# tm8_first.net
KiCad netlist of a schematic drawn in EAGLE
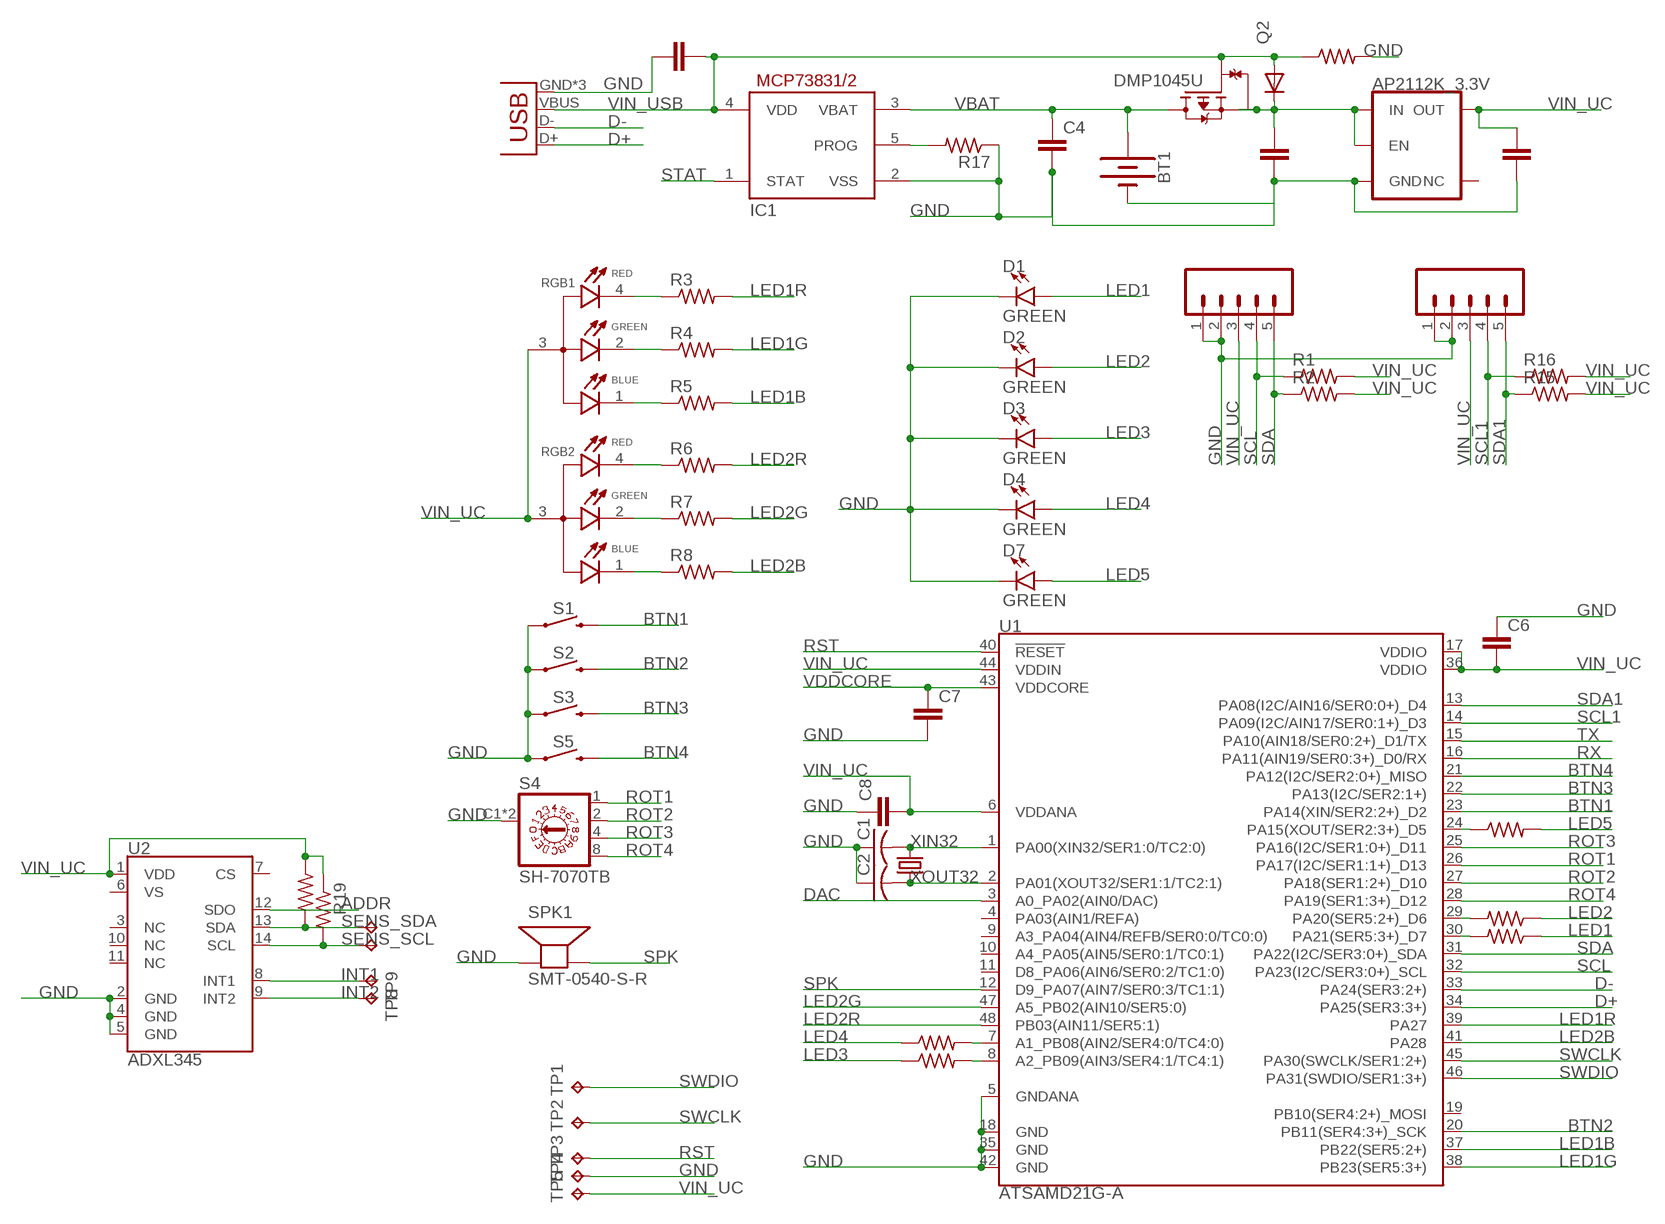
[diagram p0: schematic, sheet 1]

(export (version "E")
  (design (tool "Eeschema 10.0.6"))
  (components
    (comp (ref "AP2112K_3.3V")
      (value "3.3V")
      (footprint "eagle-import:SOT23-5")
      (libsource (lib "eagle-import") (part "V_REG_AP2112K-3.3V"))
    )
    (comp (ref "BT1")
      (value "BATTERY-20MM_SMD_4LEGS_OVERPASTE_INNER")
      (footprint "eagle-import:BATTCON_20MM_4LEGS_OVERPASTE_INNER")
      (libsource (lib "eagle-import") (part "BATTERY-20MM_SMD_4LEGS_OVERPASTE_INNER"))
    )
    (comp (ref "C1")
      (value "C-USC0603")
      (footprint "eagle-import:C0603")
      (libsource (lib "eagle-import") (part "C-USC0603"))
    )
    (comp (ref "C2")
      (value "C-USC0603")
      (footprint "eagle-import:C0603")
      (libsource (lib "eagle-import") (part "C-USC0603"))
    )
    (comp (ref "C3")
      (value "C-EUC0603")
      (footprint "eagle-import:C0603")
      (libsource (lib "eagle-import") (part "C-EUC0603"))
    )
    (comp (ref "C4")
      (value "C-EUC0603")
      (footprint "eagle-import:C0603")
      (libsource (lib "eagle-import") (part "C-EUC0603"))
    )
    (comp (ref "C5")
      (value "C-EUC0603")
      (footprint "eagle-import:C0603")
      (libsource (lib "eagle-import") (part "C-EUC0603"))
    )
    (comp (ref "C6")
      (value "C-EUC0603")
      (footprint "eagle-import:C0603")
      (libsource (lib "eagle-import") (part "C-EUC0603"))
    )
    (comp (ref "C7")
      (value "C-EUC0603")
      (footprint "eagle-import:C0603")
      (libsource (lib "eagle-import") (part "C-EUC0603"))
    )
    (comp (ref "C8")
      (value "C-EUC0603")
      (footprint "eagle-import:C0603")
      (libsource (lib "eagle-import") (part "C-EUC0603"))
    )
    (comp (ref "C9")
      (value "C-EUC0603")
      (footprint "eagle-import:C0603")
      (libsource (lib "eagle-import") (part "C-EUC0603"))
    )
    (comp (ref "D1")
      (value "GREEN")
      (footprint "eagle-import:LED-1206")
      (libsource (lib "eagle-import") (part "LED-GREEN1206"))
    )
    (comp (ref "D2")
      (value "GREEN")
      (footprint "eagle-import:LED-1206")
      (libsource (lib "eagle-import") (part "LED-GREEN1206"))
    )
    (comp (ref "D3")
      (value "GREEN")
      (footprint "eagle-import:LED-1206")
      (libsource (lib "eagle-import") (part "LED-GREEN1206"))
    )
    (comp (ref "D4")
      (value "GREEN")
      (footprint "eagle-import:LED-1206")
      (libsource (lib "eagle-import") (part "LED-GREEN1206"))
    )
    (comp (ref "D7")
      (value "GREEN")
      (footprint "eagle-import:LED-1206")
      (libsource (lib "eagle-import") (part "LED-GREEN1206"))
    )
    (comp (ref "D8")
      (value "DIODESOD-323F")
      (footprint "eagle-import:SOD-323F")
      (libsource (lib "eagle-import") (part "DIODESOD-323F"))
    )
    (comp (ref "IC1")
      (value "MCP73831/OT")
      (footprint "eagle-import:SOT23-5L")
      (libsource (lib "eagle-import") (part "MCP73831/OT"))
    )
    (comp (ref "JP2")
      (value "USB-MICROB")
      (footprint "eagle-import:USB-MICROB")
      (libsource (lib "eagle-import") (part "USB-MICROB"))
    )
    (comp (ref "LCD1")
      (value "CONN_05VERT_FEMALE_HEADER")
      (footprint "eagle-import:1X05_SMD_VERTICAL_COMBO")
      (libsource (lib "eagle-import") (part "CONN_05VERT_FEMALE_HEADER"))
    )
    (comp (ref "LCD2")
      (value "CONN_05VERT_FEMALE_HEADER")
      (footprint "eagle-import:1X05_SMD_VERTICAL_COMBO")
      (libsource (lib "eagle-import") (part "CONN_05VERT_FEMALE_HEADER"))
    )
    (comp (ref "Q2")
      (value "DMP1045U")
      (footprint "eagle-import:SOT91P240X110-3N")
      (fields (field (name "MF") "Diodes Inc."))
      (libsource (lib "eagle-import") (part "DMP1045U"))
    )
    (comp (ref "R1")
      (value "R-US_R0603")
      (footprint "eagle-import:R0603")
      (libsource (lib "eagle-import") (part "rcl_334_R-US_R0603"))
    )
    (comp (ref "R2")
      (value "R-US_R0603")
      (footprint "eagle-import:R0603")
      (libsource (lib "eagle-import") (part "rcl_334_R-US_R0603"))
    )
    (comp (ref "R3")
      (value "R-US_R0603")
      (footprint "eagle-import:R0603")
      (libsource (lib "eagle-import") (part "rcl_334_R-US_R0603"))
    )
    (comp (ref "R4")
      (value "R-US_R0603")
      (footprint "eagle-import:R0603")
      (libsource (lib "eagle-import") (part "rcl_334_R-US_R0603"))
    )
    (comp (ref "R5")
      (value "R-US_R0603")
      (footprint "eagle-import:R0603")
      (libsource (lib "eagle-import") (part "rcl_334_R-US_R0603"))
    )
    (comp (ref "R6")
      (value "R-US_R0603")
      (footprint "eagle-import:R0603")
      (libsource (lib "eagle-import") (part "rcl_334_R-US_R0603"))
    )
    (comp (ref "R7")
      (value "R-US_R0603")
      (footprint "eagle-import:R0603")
      (libsource (lib "eagle-import") (part "rcl_334_R-US_R0603"))
    )
    (comp (ref "R8")
      (value "R-US_R0603")
      (footprint "eagle-import:R0603")
      (libsource (lib "eagle-import") (part "rcl_334_R-US_R0603"))
    )
    (comp (ref "R9")
      (value "R-US_R0603")
      (footprint "eagle-import:R0603")
      (libsource (lib "eagle-import") (part "rcl_334_R-US_R0603"))
    )
    (comp (ref "R10")
      (value "R-US_R0603")
      (footprint "eagle-import:R0603")
      (libsource (lib "eagle-import") (part "rcl_334_R-US_R0603"))
    )
    (comp (ref "R11")
      (value "R-US_R0603")
      (footprint "eagle-import:R0603")
      (libsource (lib "eagle-import") (part "rcl_334_R-US_R0603"))
    )
    (comp (ref "R12")
      (value "R-US_R0603")
      (footprint "eagle-import:R0603")
      (libsource (lib "eagle-import") (part "rcl_334_R-US_R0603"))
    )
    (comp (ref "R13")
      (value "R-US_R0603")
      (footprint "eagle-import:R0603")
      (libsource (lib "eagle-import") (part "rcl_334_R-US_R0603"))
    )
    (comp (ref "R14")
      (value "R-US_R0603")
      (footprint "eagle-import:R0603")
      (libsource (lib "eagle-import") (part "R-US_R0603"))
    )
    (comp (ref "R15")
      (value "R-US_R0603")
      (footprint "eagle-import:R0603")
      (libsource (lib "eagle-import") (part "rcl_334_R-US_R0603"))
    )
    (comp (ref "R16")
      (value "R-US_R0603")
      (footprint "eagle-import:R0603")
      (libsource (lib "eagle-import") (part "rcl_334_R-US_R0603"))
    )
    (comp (ref "R17")
      (value "R-US_R0603")
      (footprint "eagle-import:R0603")
      (libsource (lib "eagle-import") (part "adafruit_25768682_R-US_R0603"))
    )
    (comp (ref "R18")
      (value "R-US_R0603")
      (footprint "eagle-import:R0603")
      (libsource (lib "eagle-import") (part "rcl_334_R-US_R0603"))
    )
    (comp (ref "R19")
      (value "R-US_R0603")
      (footprint "eagle-import:R0603")
      (libsource (lib "eagle-import") (part "rcl_334_R-US_R0603"))
    )
    (comp (ref "RGB1")
      (value "EAST1616RGBA3")
      (footprint "eagle-import:LED_EAST1616RGBA3")
      (fields (field (name "MF") "Everlight Electronics"))
      (libsource (lib "eagle-import") (part "EAST1616RGBA3"))
    )
    (comp (ref "RGB2")
      (value "EAST1616RGBA3")
      (footprint "eagle-import:LED_EAST1616RGBA3")
      (fields (field (name "MF") "Everlight Electronics"))
      (libsource (lib "eagle-import") (part "EAST1616RGBA3"))
    )
    (comp (ref "S1")
      (value "MOMENTARY-SWITCH-SPST-SMD-6.0X3.5MM")
      (footprint "eagle-import:TACTILE_SWITCH_SMD_6.0X3.5MM")
      (libsource (lib "eagle-import") (part "MOMENTARY-SWITCH-SPST-SMD-6.0X3.5MM"))
    )
    (comp (ref "S2")
      (value "MOMENTARY-SWITCH-SPST-SMD-6.0X3.5MM")
      (footprint "eagle-import:TACTILE_SWITCH_SMD_6.0X3.5MM")
      (libsource (lib "eagle-import") (part "MOMENTARY-SWITCH-SPST-SMD-6.0X3.5MM"))
    )
    (comp (ref "S3")
      (value "MOMENTARY-SWITCH-SPST-SMD-6.0X3.5MM")
      (footprint "eagle-import:TACTILE_SWITCH_SMD_6.0X3.5MM")
      (libsource (lib "eagle-import") (part "MOMENTARY-SWITCH-SPST-SMD-6.0X3.5MM"))
    )
    (comp (ref "S4")
      (value "SH-7070TB")
      (footprint "eagle-import:SH-7070B")
      (fields (field (name "MF") "Nidec Copal"))
      (libsource (lib "eagle-import") (part "SH-7070TB"))
    )
    (comp (ref "S5")
      (value "MOMENTARY-SWITCH-SPST-SMD-6.0X3.5MM")
      (footprint "eagle-import:TACTILE_SWITCH_SMD_6.0X3.5MM")
      (libsource (lib "eagle-import") (part "MOMENTARY-SWITCH-SPST-SMD-6.0X3.5MM"))
    )
    (comp (ref "SPK1")
      (value "SMT-0540-S-R")
      (footprint "eagle-import:SMT-0540-S-R")
      (fields (field (name "MF") "PUI"))
      (libsource (lib "eagle-import") (part "SMT-0540-S-R"))
    )
    (comp (ref "TP1")
      (value "TPTP10R")
      (footprint "eagle-import:TP10R")
      (libsource (lib "eagle-import") (part "TPTP10R"))
    )
    (comp (ref "TP2")
      (value "TPTP10R")
      (footprint "eagle-import:TP10R")
      (libsource (lib "eagle-import") (part "TPTP10R"))
    )
    (comp (ref "TP3")
      (value "TPTP10R")
      (footprint "eagle-import:TP10R")
      (libsource (lib "eagle-import") (part "TPTP10R"))
    )
    (comp (ref "TP4")
      (value "TPTP10R")
      (footprint "eagle-import:TP10R")
      (libsource (lib "eagle-import") (part "TPTP10R"))
    )
    (comp (ref "TP5")
      (value "TPTP10R")
      (footprint "eagle-import:TP10R")
      (libsource (lib "eagle-import") (part "TPTP10R"))
    )
    (comp (ref "TP6")
      (value "TPTP10R")
      (footprint "eagle-import:TP10R")
      (libsource (lib "eagle-import") (part "TPTP10R"))
    )
    (comp (ref "TP7")
      (value "TPTP10R")
      (footprint "eagle-import:TP10R")
      (libsource (lib "eagle-import") (part "TPTP10R"))
    )
    (comp (ref "TP8")
      (value "TPTP10R")
      (footprint "eagle-import:TP10R")
      (libsource (lib "eagle-import") (part "TPTP10R"))
    )
    (comp (ref "TP9")
      (value "TPTP10R")
      (footprint "eagle-import:TP10R")
      (libsource (lib "eagle-import") (part "TPTP10R"))
    )
    (comp (ref "U1")
      (value "ATSAMD21G-A")
      (footprint "eagle-import:TQFP-48")
      (libsource (lib "eagle-import") (part "ATSAMD21G-A"))
    )
    (comp (ref "U2")
      (value "ADXL345")
      (footprint "eagle-import:LGA-14")
      (libsource (lib "eagle-import") (part "ADXL345"))
    )
    (comp (ref "Y1")
      (value "32.768kHz")
      (footprint "eagle-import:CRYSTAL-SMD-3.2X1.5MM")
      (libsource (lib "eagle-import") (part "CRYSTAL-32.768KHZSMD-3.2X1.5"))
    )
  )
  (nets
    (net (code "1") (name "/ADDR") (class "Default")
      (node (ref "U2") (pin "12") (pinfunction "SDO_12") (pintype "bidirectional"))
    )
    (net (code "2") (name "/BTN1") (class "Default")
      (node (ref "S1") (pin "2") (pinfunction "2_2") (pintype "passive"))
      (node (ref "U1") (pin "23") (pinfunction "PA14(XIN/SER2:2+)_D2_23") (pintype "bidirectional"))
    )
    (net (code "3") (name "/BTN2") (class "Default")
      (node (ref "S2") (pin "2") (pinfunction "2_2") (pintype "passive"))
      (node (ref "U1") (pin "20") (pinfunction "PB11(SER4:3+)_SCK_20") (pintype "bidirectional"))
    )
    (net (code "4") (name "/BTN3") (class "Default")
      (node (ref "S3") (pin "2") (pinfunction "2_2") (pintype "passive"))
      (node (ref "U1") (pin "22") (pinfunction "PA13(I2C/SER2:1+)_22") (pintype "bidirectional"))
    )
    (net (code "5") (name "/BTN4") (class "Default")
      (node (ref "S5") (pin "2") (pinfunction "2_2") (pintype "passive"))
      (node (ref "U1") (pin "21") (pinfunction "PA12(I2C/SER2:0+)_MISO_21") (pintype "bidirectional"))
    )
    (net (code "6") (name "/D+") (class "Default")
      (node (ref "JP2") (pin "D+") (pinfunction "D+_D+") (pintype "bidirectional"))
      (node (ref "U1") (pin "34") (pinfunction "PA25(SER3:3+)_34") (pintype "bidirectional"))
    )
    (net (code "7") (name "/D-") (class "Default")
      (node (ref "JP2") (pin "D-") (pinfunction "D-_D-") (pintype "bidirectional"))
      (node (ref "U1") (pin "33") (pinfunction "PA24(SER3:2+)_33") (pintype "bidirectional"))
    )
    (net (code "8") (name "/DAC") (class "Default")
      (node (ref "U1") (pin "3") (pinfunction "A0_PA02(AIN0/DAC)_3") (pintype "bidirectional"))
    )
    (net (code "9") (name "/GND") (class "Default")
      (node (ref "AP2112K_3.3V") (pin "2") (pinfunction "GND_2") (pintype "input"))
      (node (ref "BT1") (pin "2") (pinfunction "-_2") (pintype "power_in"))
      (node (ref "C1") (pin "1") (pinfunction "1_1") (pintype "passive"))
      (node (ref "C2") (pin "1") (pinfunction "1_1") (pintype "passive"))
      (node (ref "C3") (pin "1") (pinfunction "1_1") (pintype "passive"))
      (node (ref "C4") (pin "2") (pinfunction "2_2") (pintype "passive"))
      (node (ref "C5") (pin "2") (pinfunction "2_2") (pintype "passive"))
      (node (ref "C6") (pin "1") (pinfunction "1_1") (pintype "passive"))
      (node (ref "C7") (pin "2") (pinfunction "2_2") (pintype "passive"))
      (node (ref "C8") (pin "1") (pinfunction "1_1") (pintype "passive"))
      (node (ref "C9") (pin "2") (pinfunction "2_2") (pintype "passive"))
      (node (ref "D1") (pin "C") (pinfunction "C_C") (pintype "passive"))
      (node (ref "D2") (pin "C") (pinfunction "C_C") (pintype "passive"))
      (node (ref "D3") (pin "C") (pinfunction "C_C") (pintype "passive"))
      (node (ref "D4") (pin "C") (pinfunction "C_C") (pintype "passive"))
      (node (ref "D7") (pin "C") (pinfunction "C_C") (pintype "passive"))
      (node (ref "IC1") (pin "2") (pinfunction "VSS_2") (pintype "power_in"))
      (node (ref "JP2") (pin "GND") (pinfunction "GND_GND") (pintype "bidirectional"))
      (node (ref "JP2") (pin "MT1") (pinfunction "GND_MT1") (pintype "bidirectional"))
      (node (ref "JP2") (pin "MT2") (pinfunction "GND_MT2") (pintype "bidirectional"))
      (node (ref "LCD1") (pin "1") (pinfunction "1_1") (pintype "passive"))
      (node (ref "LCD1") (pin "2") (pinfunction "2_2") (pintype "passive"))
      (node (ref "LCD2") (pin "1") (pinfunction "1_1") (pintype "passive"))
      (node (ref "LCD2") (pin "2") (pinfunction "2_2") (pintype "passive"))
      (node (ref "R14") (pin "2") (pinfunction "2_2") (pintype "passive"))
      (node (ref "R17") (pin "1") (pinfunction "1_1") (pintype "passive"))
      (node (ref "S1") (pin "1") (pinfunction "1_1") (pintype "passive"))
      (node (ref "S2") (pin "1") (pinfunction "1_1") (pintype "passive"))
      (node (ref "S3") (pin "1") (pinfunction "1_1") (pintype "passive"))
      (node (ref "S4") (pin "C1") (pinfunction "C_C1") (pintype "passive"))
      (node (ref "S4") (pin "C2") (pinfunction "C_C2") (pintype "passive"))
      (node (ref "S5") (pin "1") (pinfunction "1_1") (pintype "passive"))
      (node (ref "SPK1") (pin "-") (pinfunction "+_-") (pintype "passive"))
      (node (ref "TP4") (pin "TP") (pinfunction "TP_TP") (pintype "input"))
      (node (ref "U1") (pin "18") (pinfunction "GND_18") (pintype "bidirectional"))
      (node (ref "U1") (pin "35") (pinfunction "GND_35") (pintype "bidirectional"))
      (node (ref "U1") (pin "42") (pinfunction "GND_42") (pintype "bidirectional"))
      (node (ref "U1") (pin "5") (pinfunction "GNDANA_5") (pintype "bidirectional"))
      (node (ref "U2") (pin "2") (pinfunction "GND_2") (pintype "bidirectional"))
      (node (ref "U2") (pin "4") (pinfunction "GND_4") (pintype "bidirectional"))
      (node (ref "U2") (pin "5") (pinfunction "GND_5") (pintype "bidirectional"))
    )
    (net (code "10") (name "/INT1") (class "Default")
      (node (ref "TP9") (pin "TP") (pinfunction "TP_TP") (pintype "input"))
      (node (ref "U2") (pin "8") (pinfunction "INT1_8") (pintype "bidirectional"))
    )
    (net (code "11") (name "/INT2") (class "Default")
      (node (ref "TP8") (pin "TP") (pinfunction "TP_TP") (pintype "input"))
      (node (ref "U2") (pin "9") (pinfunction "INT2_9") (pintype "bidirectional"))
    )
    (net (code "12") (name "/LED1") (class "Default")
      (node (ref "D1") (pin "A") (pinfunction "A_A") (pintype "passive"))
      (node (ref "R9") (pin "1") (pinfunction "1_1") (pintype "passive"))
    )
    (net (code "13") (name "/LED1B") (class "Default")
      (node (ref "R5") (pin "2") (pinfunction "2_2") (pintype "passive"))
      (node (ref "U1") (pin "37") (pinfunction "PB22(SER5:2+)_37") (pintype "bidirectional"))
    )
    (net (code "14") (name "/LED1G") (class "Default")
      (node (ref "R4") (pin "2") (pinfunction "2_2") (pintype "passive"))
      (node (ref "U1") (pin "38") (pinfunction "PB23(SER5:3+)_38") (pintype "bidirectional"))
    )
    (net (code "15") (name "/LED1R") (class "Default")
      (node (ref "R3") (pin "2") (pinfunction "2_2") (pintype "passive"))
      (node (ref "U1") (pin "39") (pinfunction "PA27_39") (pintype "bidirectional"))
    )
    (net (code "16") (name "/LED2") (class "Default")
      (node (ref "D2") (pin "A") (pinfunction "A_A") (pintype "passive"))
      (node (ref "R10") (pin "1") (pinfunction "1_1") (pintype "passive"))
    )
    (net (code "17") (name "/LED2B") (class "Default")
      (node (ref "R8") (pin "2") (pinfunction "2_2") (pintype "passive"))
      (node (ref "U1") (pin "41") (pinfunction "PA28_41") (pintype "bidirectional"))
    )
    (net (code "18") (name "/LED2G") (class "Default")
      (node (ref "R7") (pin "2") (pinfunction "2_2") (pintype "passive"))
      (node (ref "U1") (pin "47") (pinfunction "A5_PB02(AIN10/SER5:0)_47") (pintype "bidirectional"))
    )
    (net (code "19") (name "/LED2R") (class "Default")
      (node (ref "R6") (pin "2") (pinfunction "2_2") (pintype "passive"))
      (node (ref "U1") (pin "48") (pinfunction "PB03(AIN11/SER5:1)_48") (pintype "bidirectional"))
    )
    (net (code "20") (name "/LED3") (class "Default")
      (node (ref "D3") (pin "A") (pinfunction "A_A") (pintype "passive"))
      (node (ref "R11") (pin "1") (pinfunction "1_1") (pintype "passive"))
    )
    (net (code "21") (name "/LED4") (class "Default")
      (node (ref "D4") (pin "A") (pinfunction "A_A") (pintype "passive"))
      (node (ref "R12") (pin "1") (pinfunction "1_1") (pintype "passive"))
    )
    (net (code "22") (name "/LED5") (class "Default")
      (node (ref "D7") (pin "A") (pinfunction "A_A") (pintype "passive"))
      (node (ref "R13") (pin "2") (pinfunction "2_2") (pintype "passive"))
    )
    (net (code "23") (name "/ROT1") (class "Default")
      (node (ref "S4") (pin "1") (pinfunction "1_1") (pintype "passive"))
      (node (ref "U1") (pin "26") (pinfunction "PA17(I2C/SER1:1+)_D13_26") (pintype "bidirectional"))
    )
    (net (code "24") (name "/ROT2") (class "Default")
      (node (ref "S4") (pin "2") (pinfunction "2_2") (pintype "passive"))
      (node (ref "U1") (pin "27") (pinfunction "PA18(SER1:2+)_D10_27") (pintype "bidirectional"))
    )
    (net (code "25") (name "/ROT3") (class "Default")
      (node (ref "S4") (pin "4") (pinfunction "4_4") (pintype "passive"))
      (node (ref "U1") (pin "25") (pinfunction "PA16(I2C/SER1:0+)_D11_25") (pintype "bidirectional"))
    )
    (net (code "26") (name "/ROT4") (class "Default")
      (node (ref "S4") (pin "8") (pinfunction "8_8") (pintype "passive"))
      (node (ref "U1") (pin "28") (pinfunction "PA19(SER1:3+)_D12_28") (pintype "bidirectional"))
    )
    (net (code "27") (name "/RST") (class "Default")
      (node (ref "TP3") (pin "TP") (pinfunction "TP_TP") (pintype "input"))
      (node (ref "U1") (pin "40") (pinfunction "~{RESET}_40") (pintype "bidirectional"))
    )
    (net (code "28") (name "/RX") (class "Default")
      (node (ref "U1") (pin "16") (pinfunction "PA11(AIN19/SER0:3+)_D0/RX_16") (pintype "bidirectional"))
    )
    (net (code "29") (name "/SCL") (class "Default")
      (node (ref "LCD1") (pin "4") (pinfunction "4_4") (pintype "passive"))
      (node (ref "R1") (pin "1") (pinfunction "1_1") (pintype "passive"))
      (node (ref "U1") (pin "32") (pinfunction "PA23(I2C/SER3:0+)_SCL_32") (pintype "bidirectional"))
    )
    (net (code "30") (name "/SCL1") (class "Default")
      (node (ref "LCD2") (pin "4") (pinfunction "4_4") (pintype "passive"))
      (node (ref "R16") (pin "1") (pinfunction "1_1") (pintype "passive"))
      (node (ref "U1") (pin "14") (pinfunction "PA09(I2C/AIN17/SER0:1+)_D3_14") (pintype "bidirectional"))
    )
    (net (code "31") (name "/SDA") (class "Default")
      (node (ref "LCD1") (pin "5") (pinfunction "5_5") (pintype "passive"))
      (node (ref "R2") (pin "1") (pinfunction "1_1") (pintype "passive"))
      (node (ref "U1") (pin "31") (pinfunction "PA22(I2C/SER3:0+)_SDA_31") (pintype "bidirectional"))
    )
    (net (code "32") (name "/SDA1") (class "Default")
      (node (ref "LCD2") (pin "5") (pinfunction "5_5") (pintype "passive"))
      (node (ref "R15") (pin "1") (pinfunction "1_1") (pintype "passive"))
      (node (ref "U1") (pin "13") (pinfunction "PA08(I2C/AIN16/SER0:0+)_D4_13") (pintype "bidirectional"))
    )
    (net (code "33") (name "/SENS_SCL") (class "Default")
      (node (ref "R19") (pin "2") (pinfunction "2_2") (pintype "passive"))
      (node (ref "TP6") (pin "TP") (pinfunction "TP_TP") (pintype "input"))
      (node (ref "U2") (pin "14") (pinfunction "SCL_14") (pintype "bidirectional"))
    )
    (net (code "34") (name "/SENS_SDA") (class "Default")
      (node (ref "R18") (pin "2") (pinfunction "2_2") (pintype "passive"))
      (node (ref "TP7") (pin "TP") (pinfunction "TP_TP") (pintype "input"))
      (node (ref "U2") (pin "13") (pinfunction "SDA_13") (pintype "bidirectional"))
    )
    (net (code "35") (name "/SPK") (class "Default")
      (node (ref "SPK1") (pin "+") (pinfunction "-_+") (pintype "passive"))
      (node (ref "U1") (pin "12") (pinfunction "D9_PA07(AIN7/SER0:3/TC1:1)_12") (pintype "bidirectional"))
    )
    (net (code "36") (name "/STAT") (class "Default")
      (node (ref "IC1") (pin "1") (pinfunction "STAT_1") (pintype "output"))
    )
    (net (code "37") (name "/SWCLK") (class "Default")
      (node (ref "TP2") (pin "TP") (pinfunction "TP_TP") (pintype "input"))
      (node (ref "U1") (pin "45") (pinfunction "PA30(SWCLK/SER1:2+)_45") (pintype "bidirectional"))
    )
    (net (code "38") (name "/SWDIO") (class "Default")
      (node (ref "TP1") (pin "TP") (pinfunction "TP_TP") (pintype "input"))
      (node (ref "U1") (pin "46") (pinfunction "PA31(SWDIO/SER1:3+)_46") (pintype "bidirectional"))
    )
    (net (code "39") (name "/TX") (class "Default")
      (node (ref "U1") (pin "15") (pinfunction "PA10(AIN18/SER0:2+)_D1/TX_15") (pintype "bidirectional"))
    )
    (net (code "40") (name "/VBAT") (class "Default")
      (node (ref "BT1") (pin "1") (pinfunction "+_1") (pintype "power_in"))
      (node (ref "C4") (pin "1") (pinfunction "1_1") (pintype "passive"))
      (node (ref "IC1") (pin "3") (pinfunction "VBAT_3") (pintype "bidirectional"))
      (node (ref "Q2") (pin "3") (pinfunction "D_3") (pintype "passive"))
    )
    (net (code "41") (name "/VDDCORE") (class "Default")
      (node (ref "C7") (pin "1") (pinfunction "1_1") (pintype "passive"))
      (node (ref "U1") (pin "43") (pinfunction "VDDCORE_43") (pintype "bidirectional"))
    )
    (net (code "42") (name "/VIN_UC") (class "Default")
      (node (ref "AP2112K_3.3V") (pin "5") (pinfunction "OUT_5") (pintype "passive"))
      (node (ref "C5") (pin "1") (pinfunction "1_1") (pintype "passive"))
      (node (ref "C6") (pin "2") (pinfunction "2_2") (pintype "passive"))
      (node (ref "C8") (pin "2") (pinfunction "2_2") (pintype "passive"))
      (node (ref "LCD1") (pin "3") (pinfunction "3_3") (pintype "passive"))
      (node (ref "LCD2") (pin "3") (pinfunction "3_3") (pintype "passive"))
      (node (ref "R1") (pin "2") (pinfunction "2_2") (pintype "passive"))
      (node (ref "R15") (pin "2") (pinfunction "2_2") (pintype "passive"))
      (node (ref "R16") (pin "2") (pinfunction "2_2") (pintype "passive"))
      (node (ref "R18") (pin "1") (pinfunction "1_1") (pintype "passive"))
      (node (ref "R19") (pin "1") (pinfunction "1_1") (pintype "passive"))
      (node (ref "R2") (pin "2") (pinfunction "2_2") (pintype "passive"))
      (node (ref "RGB1") (pin "3") (pinfunction "A_3") (pintype "passive"))
      (node (ref "RGB2") (pin "3") (pinfunction "A_3") (pintype "passive"))
      (node (ref "TP5") (pin "TP") (pinfunction "TP_TP") (pintype "input"))
      (node (ref "U1") (pin "17") (pinfunction "VDDIO_17") (pintype "bidirectional"))
      (node (ref "U1") (pin "36") (pinfunction "VDDIO_36") (pintype "bidirectional"))
      (node (ref "U1") (pin "44") (pinfunction "VDDIN_44") (pintype "bidirectional"))
      (node (ref "U1") (pin "6") (pinfunction "VDDANA_6") (pintype "bidirectional"))
      (node (ref "U2") (pin "1") (pinfunction "VDD_1") (pintype "bidirectional"))
    )
    (net (code "43") (name "/VIN_USB") (class "Default")
      (node (ref "C3") (pin "2") (pinfunction "2_2") (pintype "passive"))
      (node (ref "D8") (pin "A") (pinfunction "A_A") (pintype "passive"))
      (node (ref "IC1") (pin "4") (pinfunction "VDD_4") (pintype "power_in"))
      (node (ref "JP2") (pin "VBUS") (pinfunction "VBUS_VBUS") (pintype "bidirectional"))
      (node (ref "Q2") (pin "1") (pinfunction "G_1") (pintype "passive"))
      (node (ref "R14") (pin "1") (pinfunction "1_1") (pintype "passive"))
    )
    (net (code "44") (name "/XIN32") (class "Default")
      (node (ref "C1") (pin "2") (pinfunction "2_2") (pintype "passive"))
      (node (ref "U1") (pin "1") (pinfunction "PA00(XIN32/SER1:0/TC2:0)_1") (pintype "bidirectional"))
      (node (ref "Y1") (pin "P$2") (pinfunction "2_P$2") (pintype "passive"))
    )
    (net (code "45") (name "/XOUT32") (class "Default")
      (node (ref "C2") (pin "2") (pinfunction "2_2") (pintype "passive"))
      (node (ref "U1") (pin "2") (pinfunction "PA01(XOUT32/SER1:1/TC2:1)_2") (pintype "bidirectional"))
      (node (ref "Y1") (pin "P$1") (pinfunction "1_P$1") (pintype "passive"))
    )
    (net (code "46") (name "Net-(AP2112K_3.3V-EN)") (class "Default")
      (node (ref "AP2112K_3.3V") (pin "1") (pinfunction "IN_1") (pintype "input"))
      (node (ref "AP2112K_3.3V") (pin "3") (pinfunction "EN_3") (pintype "input"))
      (node (ref "C9") (pin "1") (pinfunction "1_1") (pintype "passive"))
      (node (ref "D8") (pin "C") (pinfunction "C_C") (pintype "passive"))
      (node (ref "Q2") (pin "2") (pinfunction "S_2") (pintype "passive"))
    )
    (net (code "47") (name "Net-(IC1-PROG)") (class "Default")
      (node (ref "IC1") (pin "5") (pinfunction "PROG_5") (pintype "input"))
      (node (ref "R17") (pin "2") (pinfunction "2_2") (pintype "passive"))
    )
    (net (code "48") (name "Net-(RGB1-B_C)") (class "Default")
      (node (ref "R5") (pin "1") (pinfunction "1_1") (pintype "passive"))
      (node (ref "RGB1") (pin "1") (pinfunction "B_C_1") (pintype "passive"))
    )
    (net (code "49") (name "Net-(RGB1-G_C)") (class "Default")
      (node (ref "R4") (pin "1") (pinfunction "1_1") (pintype "passive"))
      (node (ref "RGB1") (pin "2") (pinfunction "G_C_2") (pintype "passive"))
    )
    (net (code "50") (name "Net-(RGB1-R_C)") (class "Default")
      (node (ref "R3") (pin "1") (pinfunction "1_1") (pintype "passive"))
      (node (ref "RGB1") (pin "4") (pinfunction "R_C_4") (pintype "passive"))
    )
    (net (code "51") (name "Net-(RGB2-B_C)") (class "Default")
      (node (ref "R8") (pin "1") (pinfunction "1_1") (pintype "passive"))
      (node (ref "RGB2") (pin "1") (pinfunction "B_C_1") (pintype "passive"))
    )
    (net (code "52") (name "Net-(RGB2-G_C)") (class "Default")
      (node (ref "R7") (pin "1") (pinfunction "1_1") (pintype "passive"))
      (node (ref "RGB2") (pin "2") (pinfunction "G_C_2") (pintype "passive"))
    )
    (net (code "53") (name "Net-(RGB2-R_C)") (class "Default")
      (node (ref "R6") (pin "1") (pinfunction "1_1") (pintype "passive"))
      (node (ref "RGB2") (pin "4") (pinfunction "R_C_4") (pintype "passive"))
    )
    (net (code "54") (name "Net-(U1-A1_PB08(AIN2{slash}SER4:0{slash}TC4:0))") (class "Default")
      (node (ref "R12") (pin "2") (pinfunction "2_2") (pintype "passive"))
      (node (ref "U1") (pin "7") (pinfunction "A1_PB08(AIN2/SER4:0/TC4:0)_7") (pintype "bidirectional"))
    )
    (net (code "55") (name "Net-(U1-A2_PB09(AIN3{slash}SER4:1{slash}TC4:1))") (class "Default")
      (node (ref "R11") (pin "2") (pinfunction "2_2") (pintype "passive"))
      (node (ref "U1") (pin "8") (pinfunction "A2_PB09(AIN3/SER4:1/TC4:1)_8") (pintype "bidirectional"))
    )
    (net (code "56") (name "Net-(U1-PA15(XOUT{slash}SER2:3+)_D5)") (class "Default")
      (node (ref "R13") (pin "1") (pinfunction "1_1") (pintype "passive"))
      (node (ref "U1") (pin "24") (pinfunction "PA15(XOUT/SER2:3+)_D5_24") (pintype "bidirectional"))
    )
    (net (code "57") (name "Net-(U1-PA20(SER5:2+)_D6)") (class "Default")
      (node (ref "R10") (pin "2") (pinfunction "2_2") (pintype "passive"))
      (node (ref "U1") (pin "29") (pinfunction "PA20(SER5:2+)_D6_29") (pintype "bidirectional"))
    )
    (net (code "58") (name "Net-(U1-PA21(SER5:3+)_D7)") (class "Default")
      (node (ref "R9") (pin "2") (pinfunction "2_2") (pintype "passive"))
      (node (ref "U1") (pin "30") (pinfunction "PA21(SER5:3+)_D7_30") (pintype "bidirectional"))
    )
    (net (code "59") (name "unconnected-(AP2112K_3.3V-NC-Pad4)") (class "Default")
      (node (ref "AP2112K_3.3V") (pin "4") (pinfunction "NC_4") (pintype "no_connect"))
    )
    (net (code "60") (name "unconnected-(U1-A3_PA04(AIN4{slash}REFB{slash}SER0:0{slash}TC0:0)-Pad9)") (class "Default")
      (node (ref "U1") (pin "9") (pinfunction "A3_PA04(AIN4/REFB/SER0:0/TC0:0)_9") (pintype "bidirectional"))
    )
    (net (code "61") (name "unconnected-(U1-A4_PA05(AIN5{slash}SER0:1{slash}TC0:1)-Pad10)") (class "Default")
      (node (ref "U1") (pin "10") (pinfunction "A4_PA05(AIN5/SER0:1/TC0:1)_10") (pintype "bidirectional"))
    )
    (net (code "62") (name "unconnected-(U1-D8_PA06(AIN6{slash}SER0:2{slash}TC1:0)-Pad11)") (class "Default")
      (node (ref "U1") (pin "11") (pinfunction "D8_PA06(AIN6/SER0:2/TC1:0)_11") (pintype "bidirectional"))
    )
    (net (code "63") (name "unconnected-(U1-PA03(AIN1{slash}REFA)-Pad4)") (class "Default")
      (node (ref "U1") (pin "4") (pinfunction "PA03(AIN1/REFA)_4") (pintype "bidirectional"))
    )
    (net (code "64") (name "unconnected-(U1-PB10(SER4:2+)_MOSI-Pad19)") (class "Default")
      (node (ref "U1") (pin "19") (pinfunction "PB10(SER4:2+)_MOSI_19") (pintype "bidirectional"))
    )
    (net (code "65") (name "unconnected-(U2-CS-Pad7)") (class "Default")
      (node (ref "U2") (pin "7") (pinfunction "CS_7") (pintype "bidirectional"))
    )
    (net (code "66") (name "unconnected-(U2-NC-Pad3)") (class "Default")
      (node (ref "U2") (pin "3") (pinfunction "NC_3") (pintype "bidirectional"))
    )
    (net (code "67") (name "unconnected-(U2-NC-Pad10)") (class "Default")
      (node (ref "U2") (pin "10") (pinfunction "NC_10") (pintype "bidirectional"))
    )
    (net (code "68") (name "unconnected-(U2-NC-Pad11)") (class "Default")
      (node (ref "U2") (pin "11") (pinfunction "NC_11") (pintype "bidirectional"))
    )
    (net (code "69") (name "unconnected-(U2-VS-Pad6)") (class "Default")
      (node (ref "U2") (pin "6") (pinfunction "VS_6") (pintype "bidirectional"))
    )
  )
)
